# ESP32.net
KiCad netlist of a schematic drawn in Altium Designer
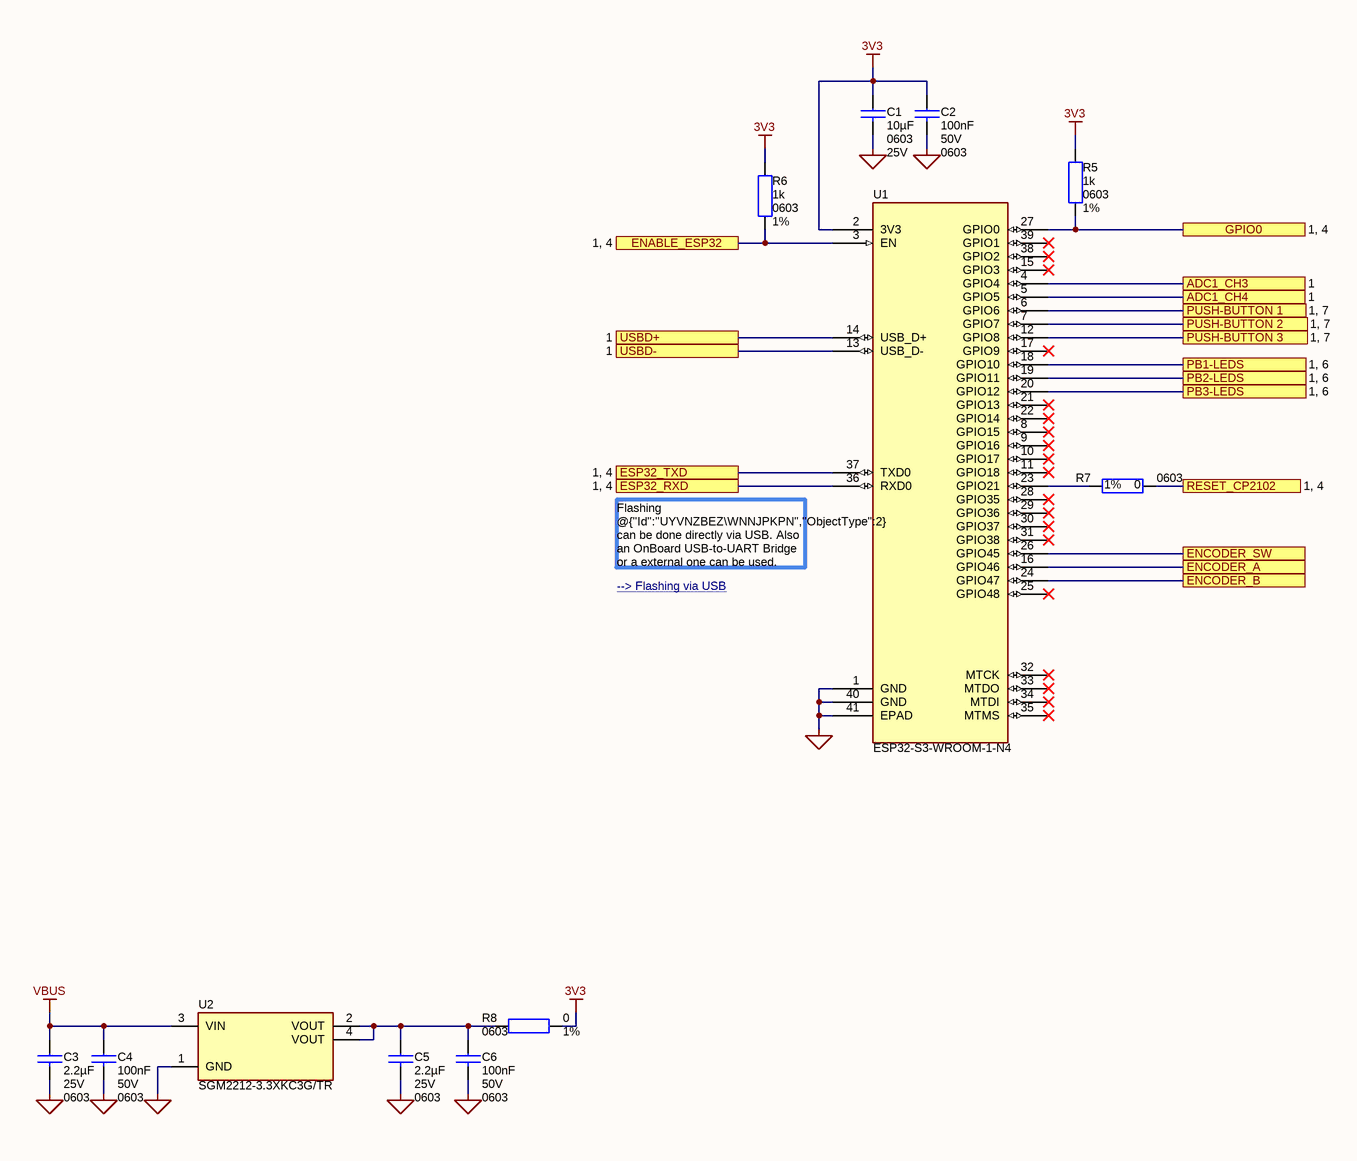
[diagram p0: ESP32.SchDoc]

(export (version "E")
  (design (tool "Eeschema 10.0.6"))
  (components
    (comp (ref "C1")
      (value "10µF")
      (footprint "CAPC0603X37L")
      (description "CAPACITOR 10 µF 0603 X5R 25V 10%")
      (fields
        (field (name "MANUFACTURER 1 PART NUMBER") "GRM188R61E106KA73D")
        (field (name "CASE/PACKAGE") "0603")
        (field (name "VOLTAGE") "25V")
        (field (name "TOLERANCE") "10%")
        (field (name "COMMENT DESIGNER") "can be substituted same values other manufacturer")
      )
      (libsource (lib "EDATRON Solutions GmbH") (part "C"))
    )
    (comp (ref "C2")
      (value "100nF")
      (footprint "CAPC0603X37L")
      (description "CAPACITOR 100 nF 0603 X7R 50V 10%")
      (fields
        (field (name "VOLTAGE") "50V")
        (field (name "MANUFACTURER 1 PART NUMBER") "C0603C104K5RACTU")
        (field (name "TOLERANCE") "10%")
        (field (name "CASE/PACKAGE") "0603")
        (field (name "COMMENT DESIGNER") "can be substituted same values other manufacturer")
      )
      (libsource (lib "EDATRON Solutions GmbH") (part "C"))
    )
    (comp (ref "C3")
      (value "2.2µF")
      (footprint "CAPC0603X37L")
      (description "CAPACITOR 2.2 µF 0603 X5R 25V 20%")
      (fields
        (field (name "MANUFACTURER 1 PART NUMBER") "GRM188R60J226MEA0D")
        (field (name "VOLTAGE") "25V")
        (field (name "CASE/PACKAGE") "0603")
        (field (name "TOLERANCE") "20%")
        (field (name "COMMENT DESIGNER") "can be substituted same values other manufacturer")
      )
      (libsource (lib "EDATRON Solutions GmbH") (part "C"))
    )
    (comp (ref "C4")
      (value "100nF")
      (footprint "CAPC0603X37L")
      (description "CAPACITOR 100 nF 0603 X7R 50V 10%")
      (fields
        (field (name "VOLTAGE") "50V")
        (field (name "MANUFACTURER 1 PART NUMBER") "C0603C104K5RACTU")
        (field (name "TOLERANCE") "10%")
        (field (name "CASE/PACKAGE") "0603")
        (field (name "COMMENT DESIGNER") "can be substituted same values other manufacturer")
      )
      (libsource (lib "EDATRON Solutions GmbH") (part "C"))
    )
    (comp (ref "C5")
      (value "2.2µF")
      (footprint "CAPC0603X37L")
      (description "CAPACITOR 2.2 µF 0603 X5R 25V 20%")
      (fields
        (field (name "MANUFACTURER 1 PART NUMBER") "GRM188R60J226MEA0D")
        (field (name "VOLTAGE") "25V")
        (field (name "CASE/PACKAGE") "0603")
        (field (name "TOLERANCE") "20%")
        (field (name "COMMENT DESIGNER") "can be substituted same values other manufacturer")
      )
      (libsource (lib "EDATRON Solutions GmbH") (part "C"))
    )
    (comp (ref "C6")
      (value "100nF")
      (footprint "CAPC0603X37L")
      (description "CAPACITOR 100 nF 0603 X7R 50V 10%")
      (fields
        (field (name "VOLTAGE") "50V")
        (field (name "MANUFACTURER 1 PART NUMBER") "C0603C104K5RACTU")
        (field (name "TOLERANCE") "10%")
        (field (name "CASE/PACKAGE") "0603")
        (field (name "COMMENT DESIGNER") "can be substituted same values other manufacturer")
      )
      (libsource (lib "EDATRON Solutions GmbH") (part "C"))
    )
    (comp (ref "R5")
      (value "1k")
      (footprint "RESC0603X21L")
      (description "RESISTOR 1K 1% 0603 100mW")
      (fields
        (field (name "CASE/PACKAGE") "0603")
        (field (name "MANUFACTURER 1 PART NUMBER") "RC0603FR-071KL")
        (field (name "POWER") "100mW")
        (field (name "TOLERANCE") "1%")
        (field (name "COMMENT DESIGNER") "can be substituted same values other manufacturers")
      )
      (libsource (lib "EDATRON Solutions GmbH") (part "R"))
    )
    (comp (ref "R6")
      (value "1k")
      (footprint "RESC0603X21L")
      (description "RESISTOR 1K 1% 0603 100mW")
      (fields
        (field (name "CASE/PACKAGE") "0603")
        (field (name "MANUFACTURER 1 PART NUMBER") "RC0603FR-071KL")
        (field (name "POWER") "100mW")
        (field (name "TOLERANCE") "1%")
        (field (name "COMMENT DESIGNER") "can be substituted same values other manufacturers")
      )
      (libsource (lib "EDATRON Solutions GmbH") (part "R"))
    )
    (comp (ref "R7")
      (value "0")
      (footprint "RESC0603X21L")
      (description "RESISTOR 0R 1% 0603 100mW")
      (fields
        (field (name "MANUFACTURER 1 PART NUMBER") "RC0603FR-070RL")
        (field (name "CASE/PACKAGE") "0603")
        (field (name "POWER") "100mW")
        (field (name "TOLERANCE") "1%")
        (field (name "COMMENT DESIGNER") "can be substituted same values other manufacturers")
      )
      (libsource (lib "") (part "R_2"))
    )
    (comp (ref "R8")
      (value "0")
      (footprint "RESC0603X21L")
      (description "RESISTOR 0R 1% 0603 100mW")
      (fields
        (field (name "POWER") "100mW")
        (field (name "CASE/PACKAGE") "0603")
        (field (name "MANUFACTURER 1 PART NUMBER") "RC0603FR-070RL")
        (field (name "TOLERANCE") "1%")
        (field (name "COMMENT DESIGNER") "can be substituted same values other manufacturers")
      )
      (libsource (lib "") (part "R_1"))
    )
    (comp (ref "U1")
      (value "ESP32-S3-WROOM-1-N4")
      (footprint "IC_ESP32-S3-WROOM-1")
      (description "ESP32-S3-WROOM-1-N4 or ESP32-S3-WROOM-1-N4R2 (PSRAM QSPI)")
      (libsource (lib "EDATRON Solutions GmbH") (part "ESP32-S3-WROOM-1-N4"))
    )
    (comp (ref "U2")
      (value "SGM2212-3.3XKC3G/TR")
      (footprint "SOT223")
      (description "LDO")
      (libsource (lib "EDATRON Solutions GmbH") (part "SGM2212-FIX"))
    )
  )
  (nets
    (net (code "1") (name "/ADC1_CH3") (class "Default")
      (node (ref "U1") (pin "4") (pinfunction "GPIO4_4") (pintype "bidirectional"))
    )
    (net (code "2") (name "/ADC1_CH4") (class "Default")
      (node (ref "U1") (pin "5") (pinfunction "GPIO5_5") (pintype "bidirectional"))
    )
    (net (code "3") (name "/ENABLE_ESP32") (class "Default")
      (node (ref "R6") (pin "2") (pinfunction "2_2") (pintype "passive"))
      (node (ref "U1") (pin "3") (pinfunction "EN_3") (pintype "input"))
    )
    (net (code "4") (name "/ENCODER_A") (class "Default")
      (node (ref "U1") (pin "16") (pinfunction "GPIO46_16") (pintype "bidirectional"))
    )
    (net (code "5") (name "/ENCODER_B") (class "Default")
      (node (ref "U1") (pin "24") (pinfunction "GPIO47_24") (pintype "bidirectional"))
    )
    (net (code "6") (name "/ENCODER_SW") (class "Default")
      (node (ref "U1") (pin "26") (pinfunction "GPIO45_26") (pintype "bidirectional"))
    )
    (net (code "7") (name "/ESP32_RXD") (class "Default")
      (node (ref "U1") (pin "36") (pinfunction "RXD0_36") (pintype "bidirectional"))
    )
    (net (code "8") (name "/ESP32_TXD") (class "Default")
      (node (ref "U1") (pin "37") (pinfunction "TXD0_37") (pintype "bidirectional"))
    )
    (net (code "9") (name "/GPIO0") (class "Default")
      (node (ref "R5") (pin "2") (pinfunction "2_2") (pintype "passive"))
      (node (ref "U1") (pin "27") (pinfunction "GPIO0_27") (pintype "bidirectional"))
    )
    (net (code "10") (name "/PB1-LEDS") (class "Default")
      (node (ref "U1") (pin "18") (pinfunction "GPIO10_18") (pintype "bidirectional"))
    )
    (net (code "11") (name "/PB2-LEDS") (class "Default")
      (node (ref "U1") (pin "19") (pinfunction "GPIO11_19") (pintype "bidirectional"))
    )
    (net (code "12") (name "/PB3-LEDS") (class "Default")
      (node (ref "U1") (pin "20") (pinfunction "GPIO12_20") (pintype "bidirectional"))
    )
    (net (code "13") (name "/PUSH-BUTTON 1") (class "Default")
      (node (ref "U1") (pin "6") (pinfunction "GPIO6_6") (pintype "bidirectional"))
    )
    (net (code "14") (name "/PUSH-BUTTON 2") (class "Default")
      (node (ref "U1") (pin "7") (pinfunction "GPIO7_7") (pintype "bidirectional"))
    )
    (net (code "15") (name "/PUSH-BUTTON 3") (class "Default")
      (node (ref "U1") (pin "12") (pinfunction "GPIO8_12") (pintype "bidirectional"))
    )
    (net (code "16") (name "/RESET_CP2102") (class "Default")
      (node (ref "R7") (pin "2") (pinfunction "2_2") (pintype "passive"))
    )
    (net (code "17") (name "/USBD+") (class "Default")
      (node (ref "U1") (pin "14") (pinfunction "USB_D+_14") (pintype "bidirectional"))
    )
    (net (code "18") (name "/USBD-") (class "Default")
      (node (ref "U1") (pin "13") (pinfunction "USB_D-_13") (pintype "bidirectional"))
    )
    (net (code "19") (name "3V3") (class "Default")
      (node (ref "C1") (pin "1") (pinfunction "1_1") (pintype "passive"))
      (node (ref "C2") (pin "1") (pinfunction "1_1") (pintype "passive"))
      (node (ref "R5") (pin "1") (pinfunction "1_1") (pintype "passive"))
      (node (ref "R6") (pin "1") (pinfunction "1_1") (pintype "passive"))
      (node (ref "R8") (pin "1") (pinfunction "1_1") (pintype "passive"))
      (node (ref "U1") (pin "2") (pinfunction "3V3_2") (pintype "power_in"))
    )
    (net (code "20") (name "GND") (class "Default")
      (node (ref "C1") (pin "2") (pinfunction "2_2") (pintype "passive"))
      (node (ref "C2") (pin "2") (pinfunction "2_2") (pintype "passive"))
      (node (ref "C3") (pin "2") (pinfunction "2_2") (pintype "passive"))
      (node (ref "C4") (pin "2") (pinfunction "2_2") (pintype "passive"))
      (node (ref "C5") (pin "2") (pinfunction "2_2") (pintype "passive"))
      (node (ref "C6") (pin "2") (pinfunction "2_2") (pintype "passive"))
      (node (ref "U1") (pin "1") (pinfunction "GND_1") (pintype "power_in"))
      (node (ref "U1") (pin "40") (pinfunction "GND_40") (pintype "power_in"))
      (node (ref "U1") (pin "41") (pinfunction "EPAD_41") (pintype "power_in"))
      (node (ref "U2") (pin "1") (pinfunction "GND_1") (pintype "power_in"))
    )
    (net (code "21") (name "Net-(C5-Pad1)") (class "Default")
      (node (ref "C5") (pin "1") (pinfunction "1_1") (pintype "passive"))
      (node (ref "C6") (pin "1") (pinfunction "1_1") (pintype "passive"))
      (node (ref "R8") (pin "2") (pinfunction "2_2") (pintype "passive"))
      (node (ref "U2") (pin "2") (pinfunction "VOUT_2") (pintype "power_in"))
      (node (ref "U2") (pin "4") (pinfunction "VOUT_4") (pintype "power_in"))
    )
    (net (code "22") (name "Net-(U1-GPIO21)") (class "Default")
      (node (ref "R7") (pin "1") (pinfunction "1_1") (pintype "passive"))
      (node (ref "U1") (pin "23") (pinfunction "GPIO21_23") (pintype "bidirectional"))
    )
    (net (code "23") (name "VBUS") (class "Default")
      (node (ref "C3") (pin "1") (pinfunction "1_1") (pintype "passive"))
      (node (ref "C4") (pin "1") (pinfunction "1_1") (pintype "passive"))
      (node (ref "U2") (pin "3") (pinfunction "VIN_3") (pintype "power_in"))
    )
    (net (code "24") (name "unconnected-(U1-GPIO1-Pad39)") (class "Default")
      (node (ref "U1") (pin "39") (pinfunction "GPIO1_39") (pintype "bidirectional+no_connect"))
    )
    (net (code "25") (name "unconnected-(U1-GPIO2-Pad38)") (class "Default")
      (node (ref "U1") (pin "38") (pinfunction "GPIO2_38") (pintype "bidirectional+no_connect"))
    )
    (net (code "26") (name "unconnected-(U1-GPIO3-Pad15)") (class "Default")
      (node (ref "U1") (pin "15") (pinfunction "GPIO3_15") (pintype "bidirectional+no_connect"))
    )
    (net (code "27") (name "unconnected-(U1-GPIO9-Pad17)") (class "Default")
      (node (ref "U1") (pin "17") (pinfunction "GPIO9_17") (pintype "bidirectional+no_connect"))
    )
    (net (code "28") (name "unconnected-(U1-GPIO13-Pad21)") (class "Default")
      (node (ref "U1") (pin "21") (pinfunction "GPIO13_21") (pintype "bidirectional+no_connect"))
    )
    (net (code "29") (name "unconnected-(U1-GPIO14-Pad22)") (class "Default")
      (node (ref "U1") (pin "22") (pinfunction "GPIO14_22") (pintype "bidirectional+no_connect"))
    )
    (net (code "30") (name "unconnected-(U1-GPIO15-Pad8)") (class "Default")
      (node (ref "U1") (pin "8") (pinfunction "GPIO15_8") (pintype "bidirectional+no_connect"))
    )
    (net (code "31") (name "unconnected-(U1-GPIO16-Pad9)") (class "Default")
      (node (ref "U1") (pin "9") (pinfunction "GPIO16_9") (pintype "bidirectional+no_connect"))
    )
    (net (code "32") (name "unconnected-(U1-GPIO17-Pad10)") (class "Default")
      (node (ref "U1") (pin "10") (pinfunction "GPIO17_10") (pintype "bidirectional+no_connect"))
    )
    (net (code "33") (name "unconnected-(U1-GPIO18-Pad11)") (class "Default")
      (node (ref "U1") (pin "11") (pinfunction "GPIO18_11") (pintype "bidirectional+no_connect"))
    )
    (net (code "34") (name "unconnected-(U1-GPIO35-Pad28)") (class "Default")
      (node (ref "U1") (pin "28") (pinfunction "GPIO35_28") (pintype "bidirectional+no_connect"))
    )
    (net (code "35") (name "unconnected-(U1-GPIO36-Pad29)") (class "Default")
      (node (ref "U1") (pin "29") (pinfunction "GPIO36_29") (pintype "bidirectional+no_connect"))
    )
    (net (code "36") (name "unconnected-(U1-GPIO37-Pad30)") (class "Default")
      (node (ref "U1") (pin "30") (pinfunction "GPIO37_30") (pintype "bidirectional+no_connect"))
    )
    (net (code "37") (name "unconnected-(U1-GPIO38-Pad31)") (class "Default")
      (node (ref "U1") (pin "31") (pinfunction "GPIO38_31") (pintype "bidirectional+no_connect"))
    )
    (net (code "38") (name "unconnected-(U1-GPIO48-Pad25)") (class "Default")
      (node (ref "U1") (pin "25") (pinfunction "GPIO48_25") (pintype "bidirectional+no_connect"))
    )
    (net (code "39") (name "unconnected-(U1-MTCK-Pad32)") (class "Default")
      (node (ref "U1") (pin "32") (pinfunction "MTCK_32") (pintype "bidirectional+no_connect"))
    )
    (net (code "40") (name "unconnected-(U1-MTDI-Pad34)") (class "Default")
      (node (ref "U1") (pin "34") (pinfunction "MTDI_34") (pintype "bidirectional+no_connect"))
    )
    (net (code "41") (name "unconnected-(U1-MTDO-Pad33)") (class "Default")
      (node (ref "U1") (pin "33") (pinfunction "MTDO_33") (pintype "bidirectional+no_connect"))
    )
    (net (code "42") (name "unconnected-(U1-MTMS-Pad35)") (class "Default")
      (node (ref "U1") (pin "35") (pinfunction "MTMS_35") (pintype "bidirectional+no_connect"))
    )
  )
)
